# ProPrj_neopixel-seven-segment-display.net
KiCad netlist of a schematic drawn in EasyEDA Pro
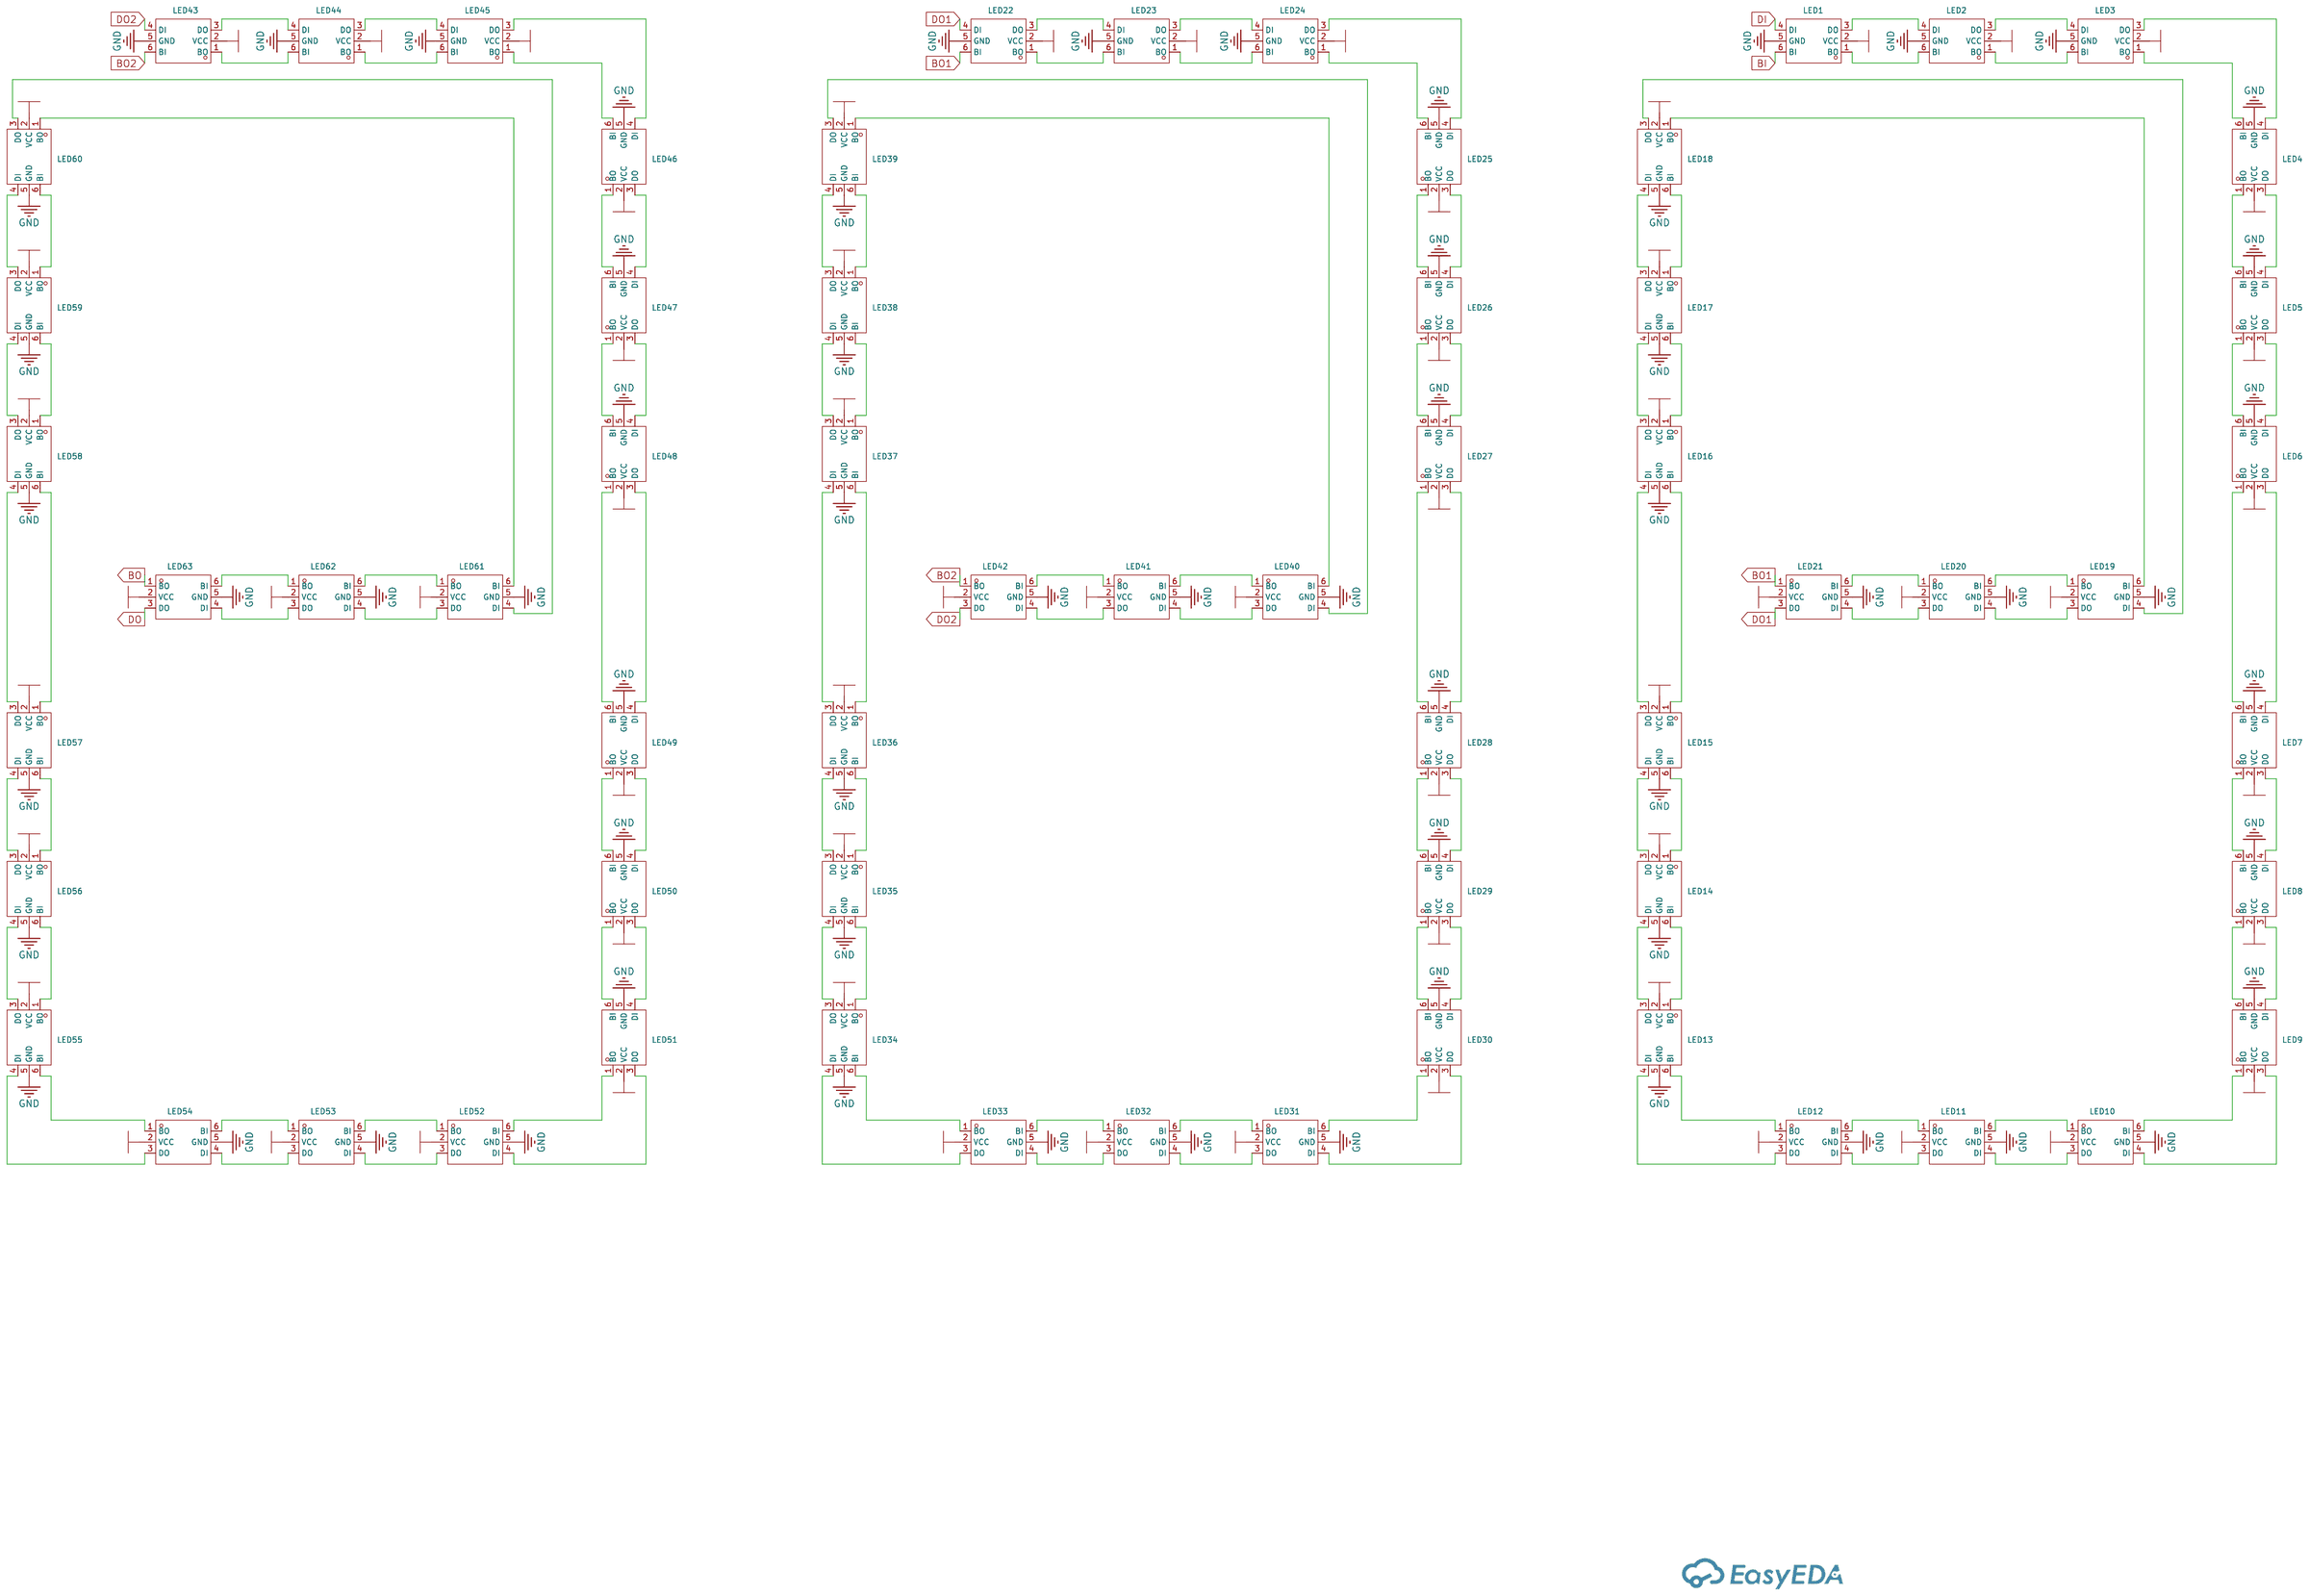
[diagram p0: LEDs]
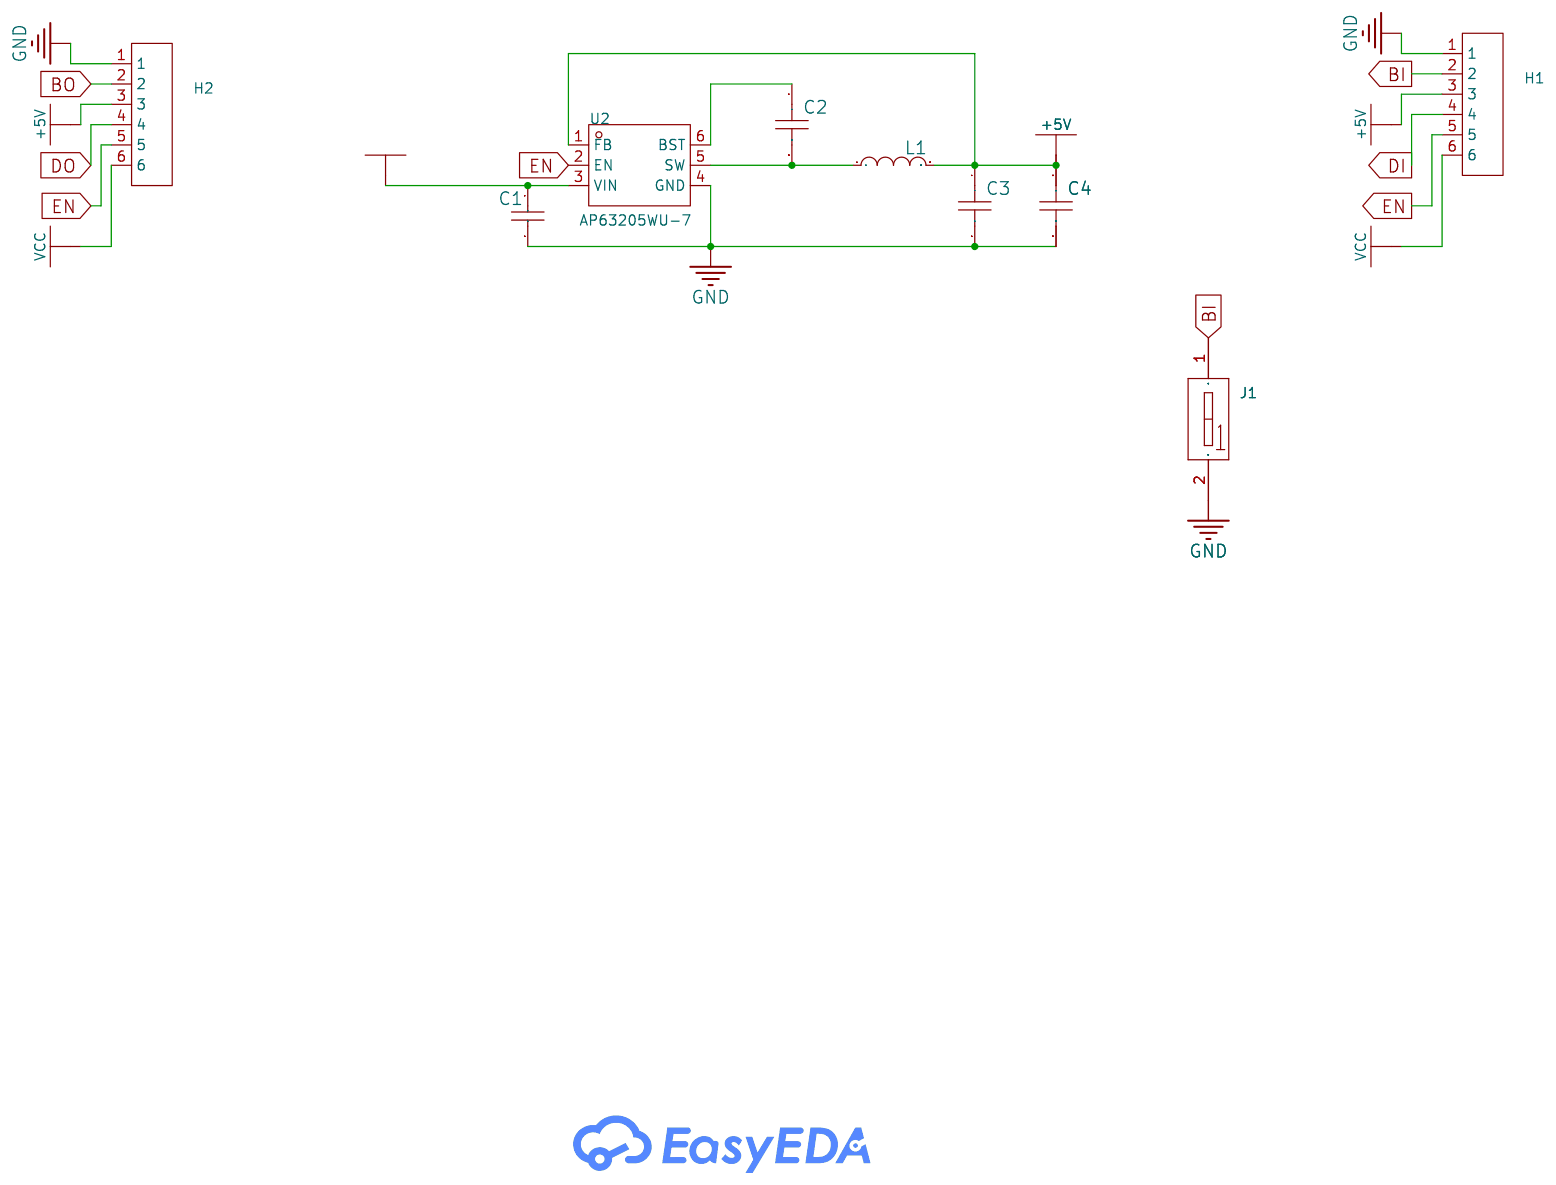
[diagram p1: Components]

(export (version "E")
  (design (tool "Eeschema 10.0.6"))
  (components
    (comp (ref "LED1")
      (value "WS2813B-V5")
      (footprint "easyedapro:LED-SMD_6P-L5.0-W5.0-TL")
      (fields (field (name "Manufacturer") "worldsemi"))
      (libsource (lib "easyedapro") (part "WS2813B-V5"))
    )
    (comp (ref "LED2")
      (value "WS2813B-V5")
      (footprint "easyedapro:LED-SMD_6P-L5.0-W5.0-TL")
      (fields (field (name "Manufacturer") "worldsemi"))
      (libsource (lib "easyedapro") (part "WS2813B-V5"))
    )
    (comp (ref "LED3")
      (value "WS2813B-V5")
      (footprint "easyedapro:LED-SMD_6P-L5.0-W5.0-TL")
      (fields (field (name "Manufacturer") "worldsemi"))
      (libsource (lib "easyedapro") (part "WS2813B-V5"))
    )
    (comp (ref "LED4")
      (value "WS2813B-V5")
      (footprint "easyedapro:LED-SMD_6P-L5.0-W5.0-TL")
      (fields (field (name "Manufacturer") "worldsemi"))
      (libsource (lib "easyedapro") (part "WS2813B-V5"))
    )
    (comp (ref "LED5")
      (value "WS2813B-V5")
      (footprint "easyedapro:LED-SMD_6P-L5.0-W5.0-TL")
      (fields (field (name "Manufacturer") "worldsemi"))
      (libsource (lib "easyedapro") (part "WS2813B-V5"))
    )
    (comp (ref "LED6")
      (value "WS2813B-V5")
      (footprint "easyedapro:LED-SMD_6P-L5.0-W5.0-TL")
      (fields (field (name "Manufacturer") "worldsemi"))
      (libsource (lib "easyedapro") (part "WS2813B-V5"))
    )
    (comp (ref "LED7")
      (value "WS2813B-V5")
      (footprint "easyedapro:LED-SMD_6P-L5.0-W5.0-TL")
      (fields (field (name "Manufacturer") "worldsemi"))
      (libsource (lib "easyedapro") (part "WS2813B-V5"))
    )
    (comp (ref "LED8")
      (value "WS2813B-V5")
      (footprint "easyedapro:LED-SMD_6P-L5.0-W5.0-TL")
      (fields (field (name "Manufacturer") "worldsemi"))
      (libsource (lib "easyedapro") (part "WS2813B-V5"))
    )
    (comp (ref "LED9")
      (value "WS2813B-V5")
      (footprint "easyedapro:LED-SMD_6P-L5.0-W5.0-TL")
      (fields (field (name "Manufacturer") "worldsemi"))
      (libsource (lib "easyedapro") (part "WS2813B-V5"))
    )
    (comp (ref "LED10")
      (value "WS2813B-V5")
      (footprint "easyedapro:LED-SMD_6P-L5.0-W5.0-TL")
      (fields (field (name "Manufacturer") "worldsemi"))
      (libsource (lib "easyedapro") (part "WS2813B-V5"))
    )
    (comp (ref "LED11")
      (value "WS2813B-V5")
      (footprint "easyedapro:LED-SMD_6P-L5.0-W5.0-TL")
      (fields (field (name "Manufacturer") "worldsemi"))
      (libsource (lib "easyedapro") (part "WS2813B-V5"))
    )
    (comp (ref "LED12")
      (value "WS2813B-V5")
      (footprint "easyedapro:LED-SMD_6P-L5.0-W5.0-TL")
      (fields (field (name "Manufacturer") "worldsemi"))
      (libsource (lib "easyedapro") (part "WS2813B-V5"))
    )
    (comp (ref "LED13")
      (value "WS2813B-V5")
      (footprint "easyedapro:LED-SMD_6P-L5.0-W5.0-TL")
      (fields (field (name "Manufacturer") "worldsemi"))
      (libsource (lib "easyedapro") (part "WS2813B-V5"))
    )
    (comp (ref "LED14")
      (value "WS2813B-V5")
      (footprint "easyedapro:LED-SMD_6P-L5.0-W5.0-TL")
      (fields (field (name "Manufacturer") "worldsemi"))
      (libsource (lib "easyedapro") (part "WS2813B-V5"))
    )
    (comp (ref "LED15")
      (value "WS2813B-V5")
      (footprint "easyedapro:LED-SMD_6P-L5.0-W5.0-TL")
      (fields (field (name "Manufacturer") "worldsemi"))
      (libsource (lib "easyedapro") (part "WS2813B-V5"))
    )
    (comp (ref "LED16")
      (value "WS2813B-V5")
      (footprint "easyedapro:LED-SMD_6P-L5.0-W5.0-TL")
      (fields (field (name "Manufacturer") "worldsemi"))
      (libsource (lib "easyedapro") (part "WS2813B-V5"))
    )
    (comp (ref "LED17")
      (value "WS2813B-V5")
      (footprint "easyedapro:LED-SMD_6P-L5.0-W5.0-TL")
      (fields (field (name "Manufacturer") "worldsemi"))
      (libsource (lib "easyedapro") (part "WS2813B-V5"))
    )
    (comp (ref "LED18")
      (value "WS2813B-V5")
      (footprint "easyedapro:LED-SMD_6P-L5.0-W5.0-TL")
      (fields (field (name "Manufacturer") "worldsemi"))
      (libsource (lib "easyedapro") (part "WS2813B-V5"))
    )
    (comp (ref "LED19")
      (value "WS2813B-V5")
      (footprint "easyedapro:LED-SMD_6P-L5.0-W5.0-TL")
      (fields (field (name "Manufacturer") "worldsemi"))
      (libsource (lib "easyedapro") (part "WS2813B-V5"))
    )
    (comp (ref "LED20")
      (value "WS2813B-V5")
      (footprint "easyedapro:LED-SMD_6P-L5.0-W5.0-TL")
      (fields (field (name "Manufacturer") "worldsemi"))
      (libsource (lib "easyedapro") (part "WS2813B-V5"))
    )
    (comp (ref "LED21")
      (value "WS2813B-V5")
      (footprint "easyedapro:LED-SMD_6P-L5.0-W5.0-TL")
      (fields (field (name "Manufacturer") "worldsemi"))
      (libsource (lib "easyedapro") (part "WS2813B-V5"))
    )
    (comp (ref "LED22")
      (value "WS2813B-V5")
      (footprint "easyedapro:LED-SMD_6P-L5.0-W5.0-TL")
      (fields (field (name "Manufacturer") "worldsemi"))
      (libsource (lib "easyedapro") (part "WS2813B-V5"))
    )
    (comp (ref "LED23")
      (value "WS2813B-V5")
      (footprint "easyedapro:LED-SMD_6P-L5.0-W5.0-TL")
      (fields (field (name "Manufacturer") "worldsemi"))
      (libsource (lib "easyedapro") (part "WS2813B-V5"))
    )
    (comp (ref "LED24")
      (value "WS2813B-V5")
      (footprint "easyedapro:LED-SMD_6P-L5.0-W5.0-TL")
      (fields (field (name "Manufacturer") "worldsemi"))
      (libsource (lib "easyedapro") (part "WS2813B-V5"))
    )
    (comp (ref "LED25")
      (value "WS2813B-V5")
      (footprint "easyedapro:LED-SMD_6P-L5.0-W5.0-TL")
      (fields (field (name "Manufacturer") "worldsemi"))
      (libsource (lib "easyedapro") (part "WS2813B-V5"))
    )
    (comp (ref "LED26")
      (value "WS2813B-V5")
      (footprint "easyedapro:LED-SMD_6P-L5.0-W5.0-TL")
      (fields (field (name "Manufacturer") "worldsemi"))
      (libsource (lib "easyedapro") (part "WS2813B-V5"))
    )
    (comp (ref "LED27")
      (value "WS2813B-V5")
      (footprint "easyedapro:LED-SMD_6P-L5.0-W5.0-TL")
      (fields (field (name "Manufacturer") "worldsemi"))
      (libsource (lib "easyedapro") (part "WS2813B-V5"))
    )
    (comp (ref "LED28")
      (value "WS2813B-V5")
      (footprint "easyedapro:LED-SMD_6P-L5.0-W5.0-TL")
      (fields (field (name "Manufacturer") "worldsemi"))
      (libsource (lib "easyedapro") (part "WS2813B-V5"))
    )
    (comp (ref "LED29")
      (value "WS2813B-V5")
      (footprint "easyedapro:LED-SMD_6P-L5.0-W5.0-TL")
      (fields (field (name "Manufacturer") "worldsemi"))
      (libsource (lib "easyedapro") (part "WS2813B-V5"))
    )
    (comp (ref "LED30")
      (value "WS2813B-V5")
      (footprint "easyedapro:LED-SMD_6P-L5.0-W5.0-TL")
      (fields (field (name "Manufacturer") "worldsemi"))
      (libsource (lib "easyedapro") (part "WS2813B-V5"))
    )
    (comp (ref "LED31")
      (value "WS2813B-V5")
      (footprint "easyedapro:LED-SMD_6P-L5.0-W5.0-TL")
      (fields (field (name "Manufacturer") "worldsemi"))
      (libsource (lib "easyedapro") (part "WS2813B-V5"))
    )
    (comp (ref "LED32")
      (value "WS2813B-V5")
      (footprint "easyedapro:LED-SMD_6P-L5.0-W5.0-TL")
      (fields (field (name "Manufacturer") "worldsemi"))
      (libsource (lib "easyedapro") (part "WS2813B-V5"))
    )
    (comp (ref "LED33")
      (value "WS2813B-V5")
      (footprint "easyedapro:LED-SMD_6P-L5.0-W5.0-TL")
      (fields (field (name "Manufacturer") "worldsemi"))
      (libsource (lib "easyedapro") (part "WS2813B-V5"))
    )
    (comp (ref "LED34")
      (value "WS2813B-V5")
      (footprint "easyedapro:LED-SMD_6P-L5.0-W5.0-TL")
      (fields (field (name "Manufacturer") "worldsemi"))
      (libsource (lib "easyedapro") (part "WS2813B-V5"))
    )
    (comp (ref "LED35")
      (value "WS2813B-V5")
      (footprint "easyedapro:LED-SMD_6P-L5.0-W5.0-TL")
      (fields (field (name "Manufacturer") "worldsemi"))
      (libsource (lib "easyedapro") (part "WS2813B-V5"))
    )
    (comp (ref "LED36")
      (value "WS2813B-V5")
      (footprint "easyedapro:LED-SMD_6P-L5.0-W5.0-TL")
      (fields (field (name "Manufacturer") "worldsemi"))
      (libsource (lib "easyedapro") (part "WS2813B-V5"))
    )
    (comp (ref "LED37")
      (value "WS2813B-V5")
      (footprint "easyedapro:LED-SMD_6P-L5.0-W5.0-TL")
      (fields (field (name "Manufacturer") "worldsemi"))
      (libsource (lib "easyedapro") (part "WS2813B-V5"))
    )
    (comp (ref "LED38")
      (value "WS2813B-V5")
      (footprint "easyedapro:LED-SMD_6P-L5.0-W5.0-TL")
      (fields (field (name "Manufacturer") "worldsemi"))
      (libsource (lib "easyedapro") (part "WS2813B-V5"))
    )
    (comp (ref "LED39")
      (value "WS2813B-V5")
      (footprint "easyedapro:LED-SMD_6P-L5.0-W5.0-TL")
      (fields (field (name "Manufacturer") "worldsemi"))
      (libsource (lib "easyedapro") (part "WS2813B-V5"))
    )
    (comp (ref "LED40")
      (value "WS2813B-V5")
      (footprint "easyedapro:LED-SMD_6P-L5.0-W5.0-TL")
      (fields (field (name "Manufacturer") "worldsemi"))
      (libsource (lib "easyedapro") (part "WS2813B-V5"))
    )
    (comp (ref "LED41")
      (value "WS2813B-V5")
      (footprint "easyedapro:LED-SMD_6P-L5.0-W5.0-TL")
      (fields (field (name "Manufacturer") "worldsemi"))
      (libsource (lib "easyedapro") (part "WS2813B-V5"))
    )
    (comp (ref "LED42")
      (value "WS2813B-V5")
      (footprint "easyedapro:LED-SMD_6P-L5.0-W5.0-TL")
      (fields (field (name "Manufacturer") "worldsemi"))
      (libsource (lib "easyedapro") (part "WS2813B-V5"))
    )
    (comp (ref "LED43")
      (value "WS2813B-V5")
      (footprint "easyedapro:LED-SMD_6P-L5.0-W5.0-TL")
      (fields (field (name "Manufacturer") "worldsemi"))
      (libsource (lib "easyedapro") (part "WS2813B-V5"))
    )
    (comp (ref "LED44")
      (value "WS2813B-V5")
      (footprint "easyedapro:LED-SMD_6P-L5.0-W5.0-TL")
      (fields (field (name "Manufacturer") "worldsemi"))
      (libsource (lib "easyedapro") (part "WS2813B-V5"))
    )
    (comp (ref "LED45")
      (value "WS2813B-V5")
      (footprint "easyedapro:LED-SMD_6P-L5.0-W5.0-TL")
      (fields (field (name "Manufacturer") "worldsemi"))
      (libsource (lib "easyedapro") (part "WS2813B-V5"))
    )
    (comp (ref "LED46")
      (value "WS2813B-V5")
      (footprint "easyedapro:LED-SMD_6P-L5.0-W5.0-TL")
      (fields (field (name "Manufacturer") "worldsemi"))
      (libsource (lib "easyedapro") (part "WS2813B-V5"))
    )
    (comp (ref "LED47")
      (value "WS2813B-V5")
      (footprint "easyedapro:LED-SMD_6P-L5.0-W5.0-TL")
      (fields (field (name "Manufacturer") "worldsemi"))
      (libsource (lib "easyedapro") (part "WS2813B-V5"))
    )
    (comp (ref "LED48")
      (value "WS2813B-V5")
      (footprint "easyedapro:LED-SMD_6P-L5.0-W5.0-TL")
      (fields (field (name "Manufacturer") "worldsemi"))
      (libsource (lib "easyedapro") (part "WS2813B-V5"))
    )
    (comp (ref "LED49")
      (value "WS2813B-V5")
      (footprint "easyedapro:LED-SMD_6P-L5.0-W5.0-TL")
      (fields (field (name "Manufacturer") "worldsemi"))
      (libsource (lib "easyedapro") (part "WS2813B-V5"))
    )
    (comp (ref "LED50")
      (value "WS2813B-V5")
      (footprint "easyedapro:LED-SMD_6P-L5.0-W5.0-TL")
      (fields (field (name "Manufacturer") "worldsemi"))
      (libsource (lib "easyedapro") (part "WS2813B-V5"))
    )
    (comp (ref "LED51")
      (value "WS2813B-V5")
      (footprint "easyedapro:LED-SMD_6P-L5.0-W5.0-TL")
      (fields (field (name "Manufacturer") "worldsemi"))
      (libsource (lib "easyedapro") (part "WS2813B-V5"))
    )
    (comp (ref "LED52")
      (value "WS2813B-V5")
      (footprint "easyedapro:LED-SMD_6P-L5.0-W5.0-TL")
      (fields (field (name "Manufacturer") "worldsemi"))
      (libsource (lib "easyedapro") (part "WS2813B-V5"))
    )
    (comp (ref "LED53")
      (value "WS2813B-V5")
      (footprint "easyedapro:LED-SMD_6P-L5.0-W5.0-TL")
      (fields (field (name "Manufacturer") "worldsemi"))
      (libsource (lib "easyedapro") (part "WS2813B-V5"))
    )
    (comp (ref "LED54")
      (value "WS2813B-V5")
      (footprint "easyedapro:LED-SMD_6P-L5.0-W5.0-TL")
      (fields (field (name "Manufacturer") "worldsemi"))
      (libsource (lib "easyedapro") (part "WS2813B-V5"))
    )
    (comp (ref "LED55")
      (value "WS2813B-V5")
      (footprint "easyedapro:LED-SMD_6P-L5.0-W5.0-TL")
      (fields (field (name "Manufacturer") "worldsemi"))
      (libsource (lib "easyedapro") (part "WS2813B-V5"))
    )
    (comp (ref "LED56")
      (value "WS2813B-V5")
      (footprint "easyedapro:LED-SMD_6P-L5.0-W5.0-TL")
      (fields (field (name "Manufacturer") "worldsemi"))
      (libsource (lib "easyedapro") (part "WS2813B-V5"))
    )
    (comp (ref "LED57")
      (value "WS2813B-V5")
      (footprint "easyedapro:LED-SMD_6P-L5.0-W5.0-TL")
      (fields (field (name "Manufacturer") "worldsemi"))
      (libsource (lib "easyedapro") (part "WS2813B-V5"))
    )
    (comp (ref "LED58")
      (value "WS2813B-V5")
      (footprint "easyedapro:LED-SMD_6P-L5.0-W5.0-TL")
      (fields (field (name "Manufacturer") "worldsemi"))
      (libsource (lib "easyedapro") (part "WS2813B-V5"))
    )
    (comp (ref "LED59")
      (value "WS2813B-V5")
      (footprint "easyedapro:LED-SMD_6P-L5.0-W5.0-TL")
      (fields (field (name "Manufacturer") "worldsemi"))
      (libsource (lib "easyedapro") (part "WS2813B-V5"))
    )
    (comp (ref "LED60")
      (value "WS2813B-V5")
      (footprint "easyedapro:LED-SMD_6P-L5.0-W5.0-TL")
      (fields (field (name "Manufacturer") "worldsemi"))
      (libsource (lib "easyedapro") (part "WS2813B-V5"))
    )
    (comp (ref "LED61")
      (value "WS2813B-V5")
      (footprint "easyedapro:LED-SMD_6P-L5.0-W5.0-TL")
      (fields (field (name "Manufacturer") "worldsemi"))
      (libsource (lib "easyedapro") (part "WS2813B-V5"))
    )
    (comp (ref "LED62")
      (value "WS2813B-V5")
      (footprint "easyedapro:LED-SMD_6P-L5.0-W5.0-TL")
      (fields (field (name "Manufacturer") "worldsemi"))
      (libsource (lib "easyedapro") (part "WS2813B-V5"))
    )
    (comp (ref "LED63")
      (value "WS2813B-V5")
      (footprint "easyedapro:LED-SMD_6P-L5.0-W5.0-TL")
      (fields (field (name "Manufacturer") "worldsemi"))
      (libsource (lib "easyedapro") (part "WS2813B-V5"))
    )
    (comp (ref "C1")
      (value "10uF")
      (footprint "easyedapro:C1210")
      (fields
        (field (name "Manufacturer Part") "CL32B106KAJNNNE")
        (field (name "Manufacturer") "SAMSUNG(三星)")
      )
      (libsource (lib "easyedapro") (part "CL32B106KAJNNNE"))
    )
    (comp (ref "C2")
      (value "100nF")
      (footprint "easyedapro:C1206")
      (fields (field (name "Manufacturer Part") "1206N104J500CT") (field (name "Manufacturer") "Walsin(华新科)"))
      (libsource (lib "easyedapro") (part "1206N104J500"))
    )
    (comp (ref "C3")
      (value "22uF")
      (footprint "easyedapro:C1210")
      (fields
        (field (name "Manufacturer Part") "CL32B226KAJNNNE")
        (field (name "Manufacturer") "SAMSUNG(三星)")
      )
      (libsource (lib "easyedapro") (part "CL32B226KAJNNNE"))
    )
    (comp (ref "C4")
      (value "22uF")
      (footprint "easyedapro:C1210")
      (fields
        (field (name "Manufacturer Part") "CL32B226KAJNNNE")
        (field (name "Manufacturer") "SAMSUNG(三星)")
      )
      (libsource (lib "easyedapro") (part "CL32B226KAJNNNE"))
    )
    (comp (ref "H1")
      (value "DB2EVC-2.54-6P-GN")
      (footprint "easyedapro:CONN-TH_6P-P2.54_DIBO_DB2EVC-2.54-6P-GN")
      (fields (field (name "Manufacturer") "DORABO(地博电气)"))
      (libsource (lib "easyedapro") (part "DB2EVC-2.54-6P-GN"))
    )
    (comp (ref "H2")
      (value "DB2EVC-2.54-6P-GN")
      (footprint "easyedapro:CONN-TH_6P-P2.54_DIBO_DB2EVC-2.54-6P-GN")
      (fields (field (name "Manufacturer") "DORABO(地博电气)"))
      (libsource (lib "easyedapro") (part "DB2EVC-2.54-6P-GN"))
    )
    (comp (ref "J1")
      (value "DSWB01LHGET")
      (footprint "easyedapro:SW-TH_DSWB01LHGET")
      (description "Type:Slide, Rocked Circuit:SPST Number of Positions:1 Lead Pitch:- Operating Life:- Color:Red")
      (fields (field (name "Manufacturer") "YE"))
      (libsource (lib "easyedapro") (part "DSWB01LHGET"))
    )
    (comp (ref "L1")
      (value "4.7uH")
      (footprint "easyedapro:IND-SMD_L3.2-W2.5_CMI3225XX")
      (fields
        (field (name "Manufacturer Part") "DFE322520FD-4R7M=P2")
        (field (name "Manufacturer") "muRata(村田)")
      )
      (libsource (lib "easyedapro") (part "DFE322520FD-4R7M=P2"))
    )
    (comp (ref "U2")
      (value "AP63205WU-7")
      (footprint "easyedapro:TSOT-23-6_L2.9-W1.6-P0.95-LS2.8-BL")
      (fields (field (name "Manufacturer") "DIODES(美台)"))
      (libsource (lib "easyedapro") (part "AP63205WU-7"))
    )
  )
  (nets
    (net (code "1") (name "+5V") (class "Default")
      (node (ref "C3") (pin "1") (pinfunction "1_1") (pintype "unspecified"))
      (node (ref "C4") (pin "1") (pinfunction "1_1") (pintype "unspecified"))
      (node (ref "H1") (pin "3") (pinfunction "3_3") (pintype "unspecified"))
      (node (ref "H2") (pin "3") (pinfunction "3_3") (pintype "unspecified"))
      (node (ref "L1") (pin "2") (pinfunction "2_2") (pintype "unspecified"))
      (node (ref "LED1") (pin "2") (pinfunction "VCC_2") (pintype "input"))
      (node (ref "LED10") (pin "2") (pinfunction "VCC_2") (pintype "input"))
      (node (ref "LED11") (pin "2") (pinfunction "VCC_2") (pintype "input"))
      (node (ref "LED12") (pin "2") (pinfunction "VCC_2") (pintype "input"))
      (node (ref "LED13") (pin "2") (pinfunction "VCC_2") (pintype "input"))
      (node (ref "LED14") (pin "2") (pinfunction "VCC_2") (pintype "input"))
      (node (ref "LED15") (pin "2") (pinfunction "VCC_2") (pintype "input"))
      (node (ref "LED16") (pin "2") (pinfunction "VCC_2") (pintype "input"))
      (node (ref "LED17") (pin "2") (pinfunction "VCC_2") (pintype "input"))
      (node (ref "LED18") (pin "2") (pinfunction "VCC_2") (pintype "input"))
      (node (ref "LED19") (pin "2") (pinfunction "VCC_2") (pintype "input"))
      (node (ref "LED2") (pin "2") (pinfunction "VCC_2") (pintype "input"))
      (node (ref "LED20") (pin "2") (pinfunction "VCC_2") (pintype "input"))
      (node (ref "LED21") (pin "2") (pinfunction "VCC_2") (pintype "input"))
      (node (ref "LED22") (pin "2") (pinfunction "VCC_2") (pintype "input"))
      (node (ref "LED23") (pin "2") (pinfunction "VCC_2") (pintype "input"))
      (node (ref "LED24") (pin "2") (pinfunction "VCC_2") (pintype "input"))
      (node (ref "LED25") (pin "2") (pinfunction "VCC_2") (pintype "input"))
      (node (ref "LED26") (pin "2") (pinfunction "VCC_2") (pintype "input"))
      (node (ref "LED27") (pin "2") (pinfunction "VCC_2") (pintype "input"))
      (node (ref "LED28") (pin "2") (pinfunction "VCC_2") (pintype "input"))
      (node (ref "LED29") (pin "2") (pinfunction "VCC_2") (pintype "input"))
      (node (ref "LED3") (pin "2") (pinfunction "VCC_2") (pintype "input"))
      (node (ref "LED30") (pin "2") (pinfunction "VCC_2") (pintype "input"))
      (node (ref "LED31") (pin "2") (pinfunction "VCC_2") (pintype "input"))
      (node (ref "LED32") (pin "2") (pinfunction "VCC_2") (pintype "input"))
      (node (ref "LED33") (pin "2") (pinfunction "VCC_2") (pintype "input"))
      (node (ref "LED34") (pin "2") (pinfunction "VCC_2") (pintype "input"))
      (node (ref "LED35") (pin "2") (pinfunction "VCC_2") (pintype "input"))
      (node (ref "LED36") (pin "2") (pinfunction "VCC_2") (pintype "input"))
      (node (ref "LED37") (pin "2") (pinfunction "VCC_2") (pintype "input"))
      (node (ref "LED38") (pin "2") (pinfunction "VCC_2") (pintype "input"))
      (node (ref "LED39") (pin "2") (pinfunction "VCC_2") (pintype "input"))
      (node (ref "LED4") (pin "2") (pinfunction "VCC_2") (pintype "input"))
      (node (ref "LED40") (pin "2") (pinfunction "VCC_2") (pintype "input"))
      (node (ref "LED41") (pin "2") (pinfunction "VCC_2") (pintype "input"))
      (node (ref "LED42") (pin "2") (pinfunction "VCC_2") (pintype "input"))
      (node (ref "LED43") (pin "2") (pinfunction "VCC_2") (pintype "input"))
      (node (ref "LED44") (pin "2") (pinfunction "VCC_2") (pintype "input"))
      (node (ref "LED45") (pin "2") (pinfunction "VCC_2") (pintype "input"))
      (node (ref "LED46") (pin "2") (pinfunction "VCC_2") (pintype "input"))
      (node (ref "LED47") (pin "2") (pinfunction "VCC_2") (pintype "input"))
      (node (ref "LED48") (pin "2") (pinfunction "VCC_2") (pintype "input"))
      (node (ref "LED49") (pin "2") (pinfunction "VCC_2") (pintype "input"))
      (node (ref "LED5") (pin "2") (pinfunction "VCC_2") (pintype "input"))
      (node (ref "LED50") (pin "2") (pinfunction "VCC_2") (pintype "input"))
      (node (ref "LED51") (pin "2") (pinfunction "VCC_2") (pintype "input"))
      (node (ref "LED52") (pin "2") (pinfunction "VCC_2") (pintype "input"))
      (node (ref "LED53") (pin "2") (pinfunction "VCC_2") (pintype "input"))
      (node (ref "LED54") (pin "2") (pinfunction "VCC_2") (pintype "input"))
      (node (ref "LED55") (pin "2") (pinfunction "VCC_2") (pintype "input"))
      (node (ref "LED56") (pin "2") (pinfunction "VCC_2") (pintype "input"))
      (node (ref "LED57") (pin "2") (pinfunction "VCC_2") (pintype "input"))
      (node (ref "LED58") (pin "2") (pinfunction "VCC_2") (pintype "input"))
      (node (ref "LED59") (pin "2") (pinfunction "VCC_2") (pintype "input"))
      (node (ref "LED6") (pin "2") (pinfunction "VCC_2") (pintype "input"))
      (node (ref "LED60") (pin "2") (pinfunction "VCC_2") (pintype "input"))
      (node (ref "LED61") (pin "2") (pinfunction "VCC_2") (pintype "input"))
      (node (ref "LED62") (pin "2") (pinfunction "VCC_2") (pintype "input"))
      (node (ref "LED63") (pin "2") (pinfunction "VCC_2") (pintype "input"))
      (node (ref "LED7") (pin "2") (pinfunction "VCC_2") (pintype "input"))
      (node (ref "LED8") (pin "2") (pinfunction "VCC_2") (pintype "input"))
      (node (ref "LED9") (pin "2") (pinfunction "VCC_2") (pintype "input"))
      (node (ref "U2") (pin "1") (pinfunction "FB_1") (pintype "input"))
    )
    (net (code "2") (name "BI") (class "Default")
      (node (ref "H1") (pin "2") (pinfunction "2_2") (pintype "unspecified"))
      (node (ref "J1") (pin "1") (pinfunction "A1_1") (pintype "input"))
      (node (ref "LED1") (pin "6") (pinfunction "BI_6") (pintype "input"))
    )
    (net (code "3") (name "BO") (class "Default")
      (node (ref "H2") (pin "2") (pinfunction "2_2") (pintype "unspecified"))
      (node (ref "LED63") (pin "1") (pinfunction "BO_1") (pintype "input"))
    )
    (net (code "4") (name "BO1") (class "Default")
      (node (ref "LED21") (pin "1") (pinfunction "BO_1") (pintype "input"))
      (node (ref "LED22") (pin "6") (pinfunction "BI_6") (pintype "input"))
    )
    (net (code "5") (name "BO2") (class "Default")
      (node (ref "LED42") (pin "1") (pinfunction "BO_1") (pintype "input"))
      (node (ref "LED43") (pin "6") (pinfunction "BI_6") (pintype "input"))
    )
    (net (code "6") (name "DI") (class "Default")
      (node (ref "H1") (pin "4") (pinfunction "4_4") (pintype "unspecified"))
      (node (ref "LED1") (pin "4") (pinfunction "DI_4") (pintype "input"))
    )
    (net (code "7") (name "DO") (class "Default")
      (node (ref "H2") (pin "4") (pinfunction "4_4") (pintype "unspecified"))
      (node (ref "LED63") (pin "3") (pinfunction "DO_3") (pintype "input"))
    )
    (net (code "8") (name "DO1") (class "Default")
      (node (ref "LED21") (pin "3") (pinfunction "DO_3") (pintype "input"))
      (node (ref "LED22") (pin "4") (pinfunction "DI_4") (pintype "input"))
    )
    (net (code "9") (name "DO2") (class "Default")
      (node (ref "LED42") (pin "3") (pinfunction "DO_3") (pintype "input"))
      (node (ref "LED43") (pin "4") (pinfunction "DI_4") (pintype "input"))
    )
    (net (code "10") (name "EN") (class "Default")
      (node (ref "H1") (pin "5") (pinfunction "5_5") (pintype "unspecified"))
      (node (ref "H2") (pin "5") (pinfunction "5_5") (pintype "unspecified"))
      (node (ref "U2") (pin "2") (pinfunction "EN_2") (pintype "input"))
    )
    (net (code "11") (name "GND") (class "Default")
      (node (ref "C1") (pin "2") (pinfunction "2_2") (pintype "input"))
      (node (ref "C3") (pin "2") (pinfunction "2_2") (pintype "unspecified"))
      (node (ref "C4") (pin "2") (pinfunction "2_2") (pintype "unspecified"))
      (node (ref "H1") (pin "1") (pinfunction "1_1") (pintype "unspecified"))
      (node (ref "H2") (pin "1") (pinfunction "1_1") (pintype "unspecified"))
      (node (ref "J1") (pin "2") (pinfunction "2_2") (pintype "input"))
      (node (ref "LED1") (pin "5") (pinfunction "GND_5") (pintype "input"))
      (node (ref "LED10") (pin "5") (pinfunction "GND_5") (pintype "input"))
      (node (ref "LED11") (pin "5") (pinfunction "GND_5") (pintype "input"))
      (node (ref "LED12") (pin "5") (pinfunction "GND_5") (pintype "input"))
      (node (ref "LED13") (pin "5") (pinfunction "GND_5") (pintype "input"))
      (node (ref "LED14") (pin "5") (pinfunction "GND_5") (pintype "input"))
      (node (ref "LED15") (pin "5") (pinfunction "GND_5") (pintype "input"))
      (node (ref "LED16") (pin "5") (pinfunction "GND_5") (pintype "input"))
      (node (ref "LED17") (pin "5") (pinfunction "GND_5") (pintype "input"))
      (node (ref "LED18") (pin "5") (pinfunction "GND_5") (pintype "input"))
      (node (ref "LED19") (pin "5") (pinfunction "GND_5") (pintype "input"))
      (node (ref "LED2") (pin "5") (pinfunction "GND_5") (pintype "input"))
      (node (ref "LED20") (pin "5") (pinfunction "GND_5") (pintype "input"))
      (node (ref "LED21") (pin "5") (pinfunction "GND_5") (pintype "input"))
      (node (ref "LED22") (pin "5") (pinfunction "GND_5") (pintype "input"))
      (node (ref "LED23") (pin "5") (pinfunction "GND_5") (pintype "input"))
      (node (ref "LED24") (pin "5") (pinfunction "GND_5") (pintype "input"))
      (node (ref "LED25") (pin "5") (pinfunction "GND_5") (pintype "input"))
      (node (ref "LED26") (pin "5") (pinfunction "GND_5") (pintype "input"))
      (node (ref "LED27") (pin "5") (pinfunction "GND_5") (pintype "input"))
      (node (ref "LED28") (pin "5") (pinfunction "GND_5") (pintype "input"))
      (node (ref "LED29") (pin "5") (pinfunction "GND_5") (pintype "input"))
      (node (ref "LED3") (pin "5") (pinfunction "GND_5") (pintype "input"))
      (node (ref "LED30") (pin "5") (pinfunction "GND_5") (pintype "input"))
      (node (ref "LED31") (pin "5") (pinfunction "GND_5") (pintype "input"))
      (node (ref "LED32") (pin "5") (pinfunction "GND_5") (pintype "input"))
      (node (ref "LED33") (pin "5") (pinfunction "GND_5") (pintype "input"))
      (node (ref "LED34") (pin "5") (pinfunction "GND_5") (pintype "input"))
      (node (ref "LED35") (pin "5") (pinfunction "GND_5") (pintype "input"))
      (node (ref "LED36") (pin "5") (pinfunction "GND_5") (pintype "input"))
      (node (ref "LED37") (pin "5") (pinfunction "GND_5") (pintype "input"))
      (node (ref "LED38") (pin "5") (pinfunction "GND_5") (pintype "input"))
      (node (ref "LED39") (pin "5") (pinfunction "GND_5") (pintype "input"))
      (node (ref "LED4") (pin "5") (pinfunction "GND_5") (pintype "input"))
      (node (ref "LED40") (pin "5") (pinfunction "GND_5") (pintype "input"))
      (node (ref "LED41") (pin "5") (pinfunction "GND_5") (pintype "input"))
      (node (ref "LED42") (pin "5") (pinfunction "GND_5") (pintype "input"))
      (node (ref "LED43") (pin "5") (pinfunction "GND_5") (pintype "input"))
      (node (ref "LED44") (pin "5") (pinfunction "GND_5") (pintype "input"))
      (node (ref "LED45") (pin "5") (pinfunction "GND_5") (pintype "input"))
      (node (ref "LED46") (pin "5") (pinfunction "GND_5") (pintype "input"))
      (node (ref "LED47") (pin "5") (pinfunction "GND_5") (pintype "input"))
      (node (ref "LED48") (pin "5") (pinfunction "GND_5") (pintype "input"))
      (node (ref "LED49") (pin "5") (pinfunction "GND_5") (pintype "input"))
      (node (ref "LED5") (pin "5") (pinfunction "GND_5") (pintype "input"))
      (node (ref "LED50") (pin "5") (pinfunction "GND_5") (pintype "input"))
      (node (ref "LED51") (pin "5") (pinfunction "GND_5") (pintype "input"))
      (node (ref "LED52") (pin "5") (pinfunction "GND_5") (pintype "input"))
      (node (ref "LED53") (pin "5") (pinfunction "GND_5") (pintype "input"))
      (node (ref "LED54") (pin "5") (pinfunction "GND_5") (pintype "input"))
      (node (ref "LED55") (pin "5") (pinfunction "GND_5") (pintype "input"))
      (node (ref "LED56") (pin "5") (pinfunction "GND_5") (pintype "input"))
      (node (ref "LED57") (pin "5") (pinfunction "GND_5") (pintype "input"))
      (node (ref "LED58") (pin "5") (pinfunction "GND_5") (pintype "input"))
      (node (ref "LED59") (pin "5") (pinfunction "GND_5") (pintype "input"))
      (node (ref "LED6") (pin "5") (pinfunction "GND_5") (pintype "input"))
      (node (ref "LED60") (pin "5") (pinfunction "GND_5") (pintype "input"))
      (node (ref "LED61") (pin "5") (pinfunction "GND_5") (pintype "input"))
      (node (ref "LED62") (pin "5") (pinfunction "GND_5") (pintype "input"))
      (node (ref "LED63") (pin "5") (pinfunction "GND_5") (pintype "input"))
      (node (ref "LED7") (pin "5") (pinfunction "GND_5") (pintype "input"))
      (node (ref "LED8") (pin "5") (pinfunction "GND_5") (pintype "input"))
      (node (ref "LED9") (pin "5") (pinfunction "GND_5") (pintype "input"))
      (node (ref "U2") (pin "4") (pinfunction "GND_4") (pintype "input"))
    )
    (net (code "12") (name "Net-(LED1-BO)") (class "Default")
      (node (ref "LED1") (pin "1") (pinfunction "BO_1") (pintype "input"))
      (node (ref "LED2") (pin "6") (pinfunction "BI_6") (pintype "input"))
    )
    (net (code "13") (name "Net-(LED1-DO)") (class "Default")
      (node (ref "LED1") (pin "3") (pinfunction "DO_3") (pintype "input"))
      (node (ref "LED2") (pin "4") (pinfunction "DI_4") (pintype "input"))
    )
    (net (code "14") (name "Net-(LED2-BO)") (class "Default")
      (node (ref "LED2") (pin "1") (pinfunction "BO_1") (pintype "input"))
      (node (ref "LED3") (pin "6") (pinfunction "BI_6") (pintype "input"))
    )
    (net (code "15") (name "Net-(LED2-DO)") (class "Default")
      (node (ref "LED2") (pin "3") (pinfunction "DO_3") (pintype "input"))
      (node (ref "LED3") (pin "4") (pinfunction "DI_4") (pintype "input"))
    )
    (net (code "16") (name "Net-(LED3-BO)") (class "Default")
      (node (ref "LED3") (pin "1") (pinfunction "BO_1") (pintype "input"))
      (node (ref "LED4") (pin "6") (pinfunction "BI_6") (pintype "input"))
    )
    (net (code "17") (name "Net-(LED3-DO)") (class "Default")
      (node (ref "LED3") (pin "3") (pinfunction "DO_3") (pintype "input"))
      (node (ref "LED4") (pin "4") (pinfunction "DI_4") (pintype "input"))
    )
    (net (code "18") (name "Net-(LED4-BO)") (class "Default")
      (node (ref "LED4") (pin "1") (pinfunction "BO_1") (pintype "input"))
      (node (ref "LED5") (pin "6") (pinfunction "BI_6") (pintype "input"))
    )
    (net (code "19") (name "Net-(LED4-DO)") (class "Default")
      (node (ref "LED4") (pin "3") (pinfunction "DO_3") (pintype "input"))
      (node (ref "LED5") (pin "4") (pinfunction "DI_4") (pintype "input"))
    )
    (net (code "20") (name "Net-(LED5-BO)") (class "Default")
      (node (ref "LED5") (pin "1") (pinfunction "BO_1") (pintype "input"))
      (node (ref "LED6") (pin "6") (pinfunction "BI_6") (pintype "input"))
    )
    (net (code "21") (name "Net-(LED5-DO)") (class "Default")
      (node (ref "LED5") (pin "3") (pinfunction "DO_3") (pintype "input"))
      (node (ref "LED6") (pin "4") (pinfunction "DI_4") (pintype "input"))
    )
    (net (code "22") (name "Net-(LED6-BO)") (class "Default")
      (node (ref "LED6") (pin "1") (pinfunction "BO_1") (pintype "input"))
      (node (ref "LED7") (pin "6") (pinfunction "BI_6") (pintype "input"))
    )
    (net (code "23") (name "Net-(LED6-DO)") (class "Default")
      (node (ref "LED6") (pin "3") (pinfunction "DO_3") (pintype "input"))
      (node (ref "LED7") (pin "4") (pinfunction "DI_4") (pintype "input"))
    )
    (net (code "24") (name "Net-(LED7-BO)") (class "Default")
      (node (ref "LED7") (pin "1") (pinfunction "BO_1") (pintype "input"))
      (node (ref "LED8") (pin "6") (pinfunction "BI_6") (pintype "input"))
    )
    (net (code "25") (name "Net-(LED7-DO)") (class "Default")
      (node (ref "LED7") (pin "3") (pinfunction "DO_3") (pintype "input"))
      (node (ref "LED8") (pin "4") (pinfunction "DI_4") (pintype "input"))
    )
    (net (code "26") (name "Net-(LED8-BO)") (class "Default")
      (node (ref "LED8") (pin "1") (pinfunction "BO_1") (pintype "input"))
      (node (ref "LED9") (pin "6") (pinfunction "BI_6") (pintype "input"))
    )
    (net (code "27") (name "Net-(LED8-DO)") (class "Default")
      (node (ref "LED8") (pin "3") (pinfunction "DO_3") (pintype "input"))
      (node (ref "LED9") (pin "4") (pinfunction "DI_4") (pintype "input"))
    )
    (net (code "28") (name "Net-(LED10-BI)") (class "Default")
      (node (ref "LED10") (pin "6") (pinfunction "BI_6") (pintype "input"))
      (node (ref "LED9") (pin "1") (pinfunction "BO_1") (pintype "input"))
    )
    (net (code "29") (name "Net-(LED10-BO)") (class "Default")
      (node (ref "LED10") (pin "1") (pinfunction "BO_1") (pintype "input"))
      (node (ref "LED11") (pin "6") (pinfunction "BI_6") (pintype "input"))
    )
    (net (code "30") (name "Net-(LED10-DI)") (class "Default")
      (node (ref "LED10") (pin "4") (pinfunction "DI_4") (pintype "input"))
      (node (ref "LED9") (pin "3") (pinfunction "DO_3") (pintype "input"))
    )
    (net (code "31") (name "Net-(LED10-DO)") (class "Default")
      (node (ref "LED10") (pin "3") (pinfunction "DO_3") (pintype "input"))
      (node (ref "LED11") (pin "4") (pinfunction "DI_4") (pintype "input"))
    )
    (net (code "32") (name "Net-(LED11-BO)") (class "Default")
      (node (ref "LED11") (pin "1") (pinfunction "BO_1") (pintype "input"))
      (node (ref "LED12") (pin "6") (pinfunction "BI_6") (pintype "input"))
    )
    (net (code "33") (name "Net-(LED11-DO)") (class "Default")
      (node (ref "LED11") (pin "3") (pinfunction "DO_3") (pintype "input"))
      (node (ref "LED12") (pin "4") (pinfunction "DI_4") (pintype "input"))
    )
    (net (code "34") (name "Net-(LED12-BO)") (class "Default")
      (node (ref "LED12") (pin "1") (pinfunction "BO_1") (pintype "input"))
      (node (ref "LED13") (pin "6") (pinfunction "BI_6") (pintype "input"))
    )
    (net (code "35") (name "Net-(LED12-DO)") (class "Default")
      (node (ref "LED12") (pin "3") (pinfunction "DO_3") (pintype "input"))
      (node (ref "LED13") (pin "4") (pinfunction "DI_4") (pintype "input"))
    )
    (net (code "36") (name "Net-(LED13-BO)") (class "Default")
      (node (ref "LED13") (pin "1") (pinfunction "BO_1") (pintype "input"))
      (node (ref "LED14") (pin "6") (pinfunction "BI_6") (pintype "input"))
    )
    (net (code "37") (name "Net-(LED13-DO)") (class "Default")
      (node (ref "LED13") (pin "3") (pinfunction "DO_3") (pintype "input"))
      (node (ref "LED14") (pin "4") (pinfunction "DI_4") (pintype "input"))
    )
    (net (code "38") (name "Net-(LED14-BO)") (class "Default")
      (node (ref "LED14") (pin "1") (pinfunction "BO_1") (pintype "input"))
      (node (ref "LED15") (pin "6") (pinfunction "BI_6") (pintype "input"))
    )
    (net (code "39") (name "Net-(LED14-DO)") (class "Default")
      (node (ref "LED14") (pin "3") (pinfunction "DO_3") (pintype "input"))
      (node (ref "LED15") (pin "4") (pinfunction "DI_4") (pintype "input"))
    )
    (net (code "40") (name "Net-(LED15-BO)") (class "Default")
      (node (ref "LED15") (pin "1") (pinfunction "BO_1") (pintype "input"))
      (node (ref "LED16") (pin "6") (pinfunction "BI_6") (pintype "input"))
    )
    (net (code "41") (name "Net-(LED15-DO)") (class "Default")
      (node (ref "LED15") (pin "3") (pinfunction "DO_3") (pintype "input"))
      (node (ref "LED16") (pin "4") (pinfunction "DI_4") (pintype "input"))
    )
    (net (code "42") (name "Net-(LED16-BO)") (class "Default")
      (node (ref "LED16") (pin "1") (pinfunction "BO_1") (pintype "input"))
      (node (ref "LED17") (pin "6") (pinfunction "BI_6") (pintype "input"))
    )
    (net (code "43") (name "Net-(LED16-DO)") (class "Default")
      (node (ref "LED16") (pin "3") (pinfunction "DO_3") (pintype "input"))
      (node (ref "LED17") (pin "4") (pinfunction "DI_4") (pintype "input"))
    )
    (net (code "44") (name "Net-(LED17-BO)") (class "Default")
      (node (ref "LED17") (pin "1") (pinfunction "BO_1") (pintype "input"))
      (node (ref "LED18") (pin "6") (pinfunction "BI_6") (pintype "input"))
    )
    (net (code "45") (name "Net-(LED17-DO)") (class "Default")
      (node (ref "LED17") (pin "3") (pinfunction "DO_3") (pintype "input"))
      (node (ref "LED18") (pin "4") (pinfunction "DI_4") (pintype "input"))
    )
    (net (code "46") (name "Net-(LED18-BO)") (class "Default")
      (node (ref "LED18") (pin "1") (pinfunction "BO_1") (pintype "input"))
      (node (ref "LED19") (pin "6") (pinfunction "BI_6") (pintype "input"))
    )
    (net (code "47") (name "Net-(LED18-DO)") (class "Default")
      (node (ref "LED18") (pin "3") (pinfunction "DO_3") (pintype "input"))
      (node (ref "LED19") (pin "4") (pinfunction "DI_4") (pintype "input"))
    )
    (net (code "48") (name "Net-(LED19-BO)") (class "Default")
      (node (ref "LED19") (pin "1") (pinfunction "BO_1") (pintype "input"))
      (node (ref "LED20") (pin "6") (pinfunction "BI_6") (pintype "input"))
    )
    (net (code "49") (name "Net-(LED19-DO)") (class "Default")
      (node (ref "LED19") (pin "3") (pinfunction "DO_3") (pintype "input"))
      (node (ref "LED20") (pin "4") (pinfunction "DI_4") (pintype "input"))
    )
    (net (code "50") (name "Net-(LED20-BO)") (class "Default")
      (node (ref "LED20") (pin "1") (pinfunction "BO_1") (pintype "input"))
      (node (ref "LED21") (pin "6") (pinfunction "BI_6") (pintype "input"))
    )
    (net (code "51") (name "Net-(LED20-DO)") (class "Default")
      (node (ref "LED20") (pin "3") (pinfunction "DO_3") (pintype "input"))
      (node (ref "LED21") (pin "4") (pinfunction "DI_4") (pintype "input"))
    )
    (net (code "52") (name "Net-(LED22-BO)") (class "Default")
      (node (ref "LED22") (pin "1") (pinfunction "BO_1") (pintype "input"))
      (node (ref "LED23") (pin "6") (pinfunction "BI_6") (pintype "input"))
    )
    (net (code "53") (name "Net-(LED22-DO)") (class "Default")
      (node (ref "LED22") (pin "3") (pinfunction "DO_3") (pintype "input"))
      (node (ref "LED23") (pin "4") (pinfunction "DI_4") (pintype "input"))
    )
    (net (code "54") (name "Net-(LED23-BO)") (class "Default")
      (node (ref "LED23") (pin "1") (pinfunction "BO_1") (pintype "input"))
      (node (ref "LED24") (pin "6") (pinfunction "BI_6") (pintype "input"))
    )
    (net (code "55") (name "Net-(LED23-DO)") (class "Default")
      (node (ref "LED23") (pin "3") (pinfunction "DO_3") (pintype "input"))
      (node (ref "LED24") (pin "4") (pinfunction "DI_4") (pintype "input"))
    )
    (net (code "56") (name "Net-(LED24-BO)") (class "Default")
      (node (ref "LED24") (pin "1") (pinfunction "BO_1") (pintype "input"))
      (node (ref "LED25") (pin "6") (pinfunction "BI_6") (pintype "input"))
    )
    (net (code "57") (name "Net-(LED24-DO)") (class "Default")
      (node (ref "LED24") (pin "3") (pinfunction "DO_3") (pintype "input"))
      (node (ref "LED25") (pin "4") (pinfunction "DI_4") (pintype "input"))
    )
    (net (code "58") (name "Net-(LED25-BO)") (class "Default")
      (node (ref "LED25") (pin "1") (pinfunction "BO_1") (pintype "input"))
      (node (ref "LED26") (pin "6") (pinfunction "BI_6") (pintype "input"))
    )
    (net (code "59") (name "Net-(LED25-DO)") (class "Default")
      (node (ref "LED25") (pin "3") (pinfunction "DO_3") (pintype "input"))
      (node (ref "LED26") (pin "4") (pinfunction "DI_4") (pintype "input"))
    )
    (net (code "60") (name "Net-(LED26-BO)") (class "Default")
      (node (ref "LED26") (pin "1") (pinfunction "BO_1") (pintype "input"))
      (node (ref "LED27") (pin "6") (pinfunction "BI_6") (pintype "input"))
    )
    (net (code "61") (name "Net-(LED26-DO)") (class "Default")
      (node (ref "LED26") (pin "3") (pinfunction "DO_3") (pintype "input"))
      (node (ref "LED27") (pin "4") (pinfunction "DI_4") (pintype "input"))
    )
    (net (code "62") (name "Net-(LED27-BO)") (class "Default")
      (node (ref "LED27") (pin "1") (pinfunction "BO_1") (pintype "input"))
      (node (ref "LED28") (pin "6") (pinfunction "BI_6") (pintype "input"))
    )
    (net (code "63") (name "Net-(LED27-DO)") (class "Default")
      (node (ref "LED27") (pin "3") (pinfunction "DO_3") (pintype "input"))
      (node (ref "LED28") (pin "4") (pinfunction "DI_4") (pintype "input"))
    )
    (net (code "64") (name "Net-(LED28-BO)") (class "Default")
      (node (ref "LED28") (pin "1") (pinfunction "BO_1") (pintype "input"))
      (node (ref "LED29") (pin "6") (pinfunction "BI_6") (pintype "input"))
    )
    (net (code "65") (name "Net-(LED28-DO)") (class "Default")
      (node (ref "LED28") (pin "3") (pinfunction "DO_3") (pintype "input"))
      (node (ref "LED29") (pin "4") (pinfunction "DI_4") (pintype "input"))
    )
    (net (code "66") (name "Net-(LED29-BO)") (class "Default")
      (node (ref "LED29") (pin "1") (pinfunction "BO_1") (pintype "input"))
      (node (ref "LED30") (pin "6") (pinfunction "BI_6") (pintype "input"))
    )
    (net (code "67") (name "Net-(LED29-DO)") (class "Default")
      (node (ref "LED29") (pin "3") (pinfunction "DO_3") (pintype "input"))
      (node (ref "LED30") (pin "4") (pinfunction "DI_4") (pintype "input"))
    )
    (net (code "68") (name "Net-(LED30-BO)") (class "Default")
      (node (ref "LED30") (pin "1") (pinfunction "BO_1") (pintype "input"))
      (node (ref "LED31") (pin "6") (pinfunction "BI_6") (pintype "input"))
    )
    (net (code "69") (name "Net-(LED30-DO)") (class "Default")
      (node (ref "LED30") (pin "3") (pinfunction "DO_3") (pintype "input"))
      (node (ref "LED31") (pin "4") (pinfunction "DI_4") (pintype "input"))
    )
    (net (code "70") (name "Net-(LED31-BO)") (class "Default")
      (node (ref "LED31") (pin "1") (pinfunction "BO_1") (pintype "input"))
      (node (ref "LED32") (pin "6") (pinfunction "BI_6") (pintype "input"))
    )
    (net (code "71") (name "Net-(LED31-DO)") (class "Default")
      (node (ref "LED31") (pin "3") (pinfunction "DO_3") (pintype "input"))
      (node (ref "LED32") (pin "4") (pinfunction "DI_4") (pintype "input"))
    )
    (net (code "72") (name "Net-(LED32-BO)") (class "Default")
      (node (ref "LED32") (pin "1") (pinfunction "BO_1") (pintype "input"))
      (node (ref "LED33") (pin "6") (pinfunction "BI_6") (pintype "input"))
    )
    (net (code "73") (name "Net-(LED32-DO)") (class "Default")
      (node (ref "LED32") (pin "3") (pinfunction "DO_3") (pintype "input"))
      (node (ref "LED33") (pin "4") (pinfunction "DI_4") (pintype "input"))
    )
    (net (code "74") (name "Net-(LED33-BO)") (class "Default")
      (node (ref "LED33") (pin "1") (pinfunction "BO_1") (pintype "input"))
      (node (ref "LED34") (pin "6") (pinfunction "BI_6") (pintype "input"))
    )
    (net (code "75") (name "Net-(LED33-DO)") (class "Default")
      (node (ref "LED33") (pin "3") (pinfunction "DO_3") (pintype "input"))
      (node (ref "LED34") (pin "4") (pinfunction "DI_4") (pintype "input"))
    )
    (net (code "76") (name "Net-(LED34-BO)") (class "Default")
      (node (ref "LED34") (pin "1") (pinfunction "BO_1") (pintype "input"))
      (node (ref "LED35") (pin "6") (pinfunction "BI_6") (pintype "input"))
    )
    (net (code "77") (name "Net-(LED34-DO)") (class "Default")
      (node (ref "LED34") (pin "3") (pinfunction "DO_3") (pintype "input"))
      (node (ref "LED35") (pin "4") (pinfunction "DI_4") (pintype "input"))
    )
    (net (code "78") (name "Net-(LED35-BO)") (class "Default")
      (node (ref "LED35") (pin "1") (pinfunction "BO_1") (pintype "input"))
      (node (ref "LED36") (pin "6") (pinfunction "BI_6") (pintype "input"))
    )
    (net (code "79") (name "Net-(LED35-DO)") (class "Default")
      (node (ref "LED35") (pin "3") (pinfunction "DO_3") (pintype "input"))
      (node (ref "LED36") (pin "4") (pinfunction "DI_4") (pintype "input"))
    )
    (net (code "80") (name "Net-(LED36-BO)") (class "Default")
      (node (ref "LED36") (pin "1") (pinfunction "BO_1") (pintype "input"))
      (node (ref "LED37") (pin "6") (pinfunction "BI_6") (pintype "input"))
    )
    (net (code "81") (name "Net-(LED36-DO)") (class "Default")
      (node (ref "LED36") (pin "3") (pinfunction "DO_3") (pintype "input"))
      (node (ref "LED37") (pin "4") (pinfunction "DI_4") (pintype "input"))
    )
    (net (code "82") (name "Net-(LED37-BO)") (class "Default")
      (node (ref "LED37") (pin "1") (pinfunction "BO_1") (pintype "input"))
      (node (ref "LED38") (pin "6") (pinfunction "BI_6") (pintype "input"))
    )
    (net (code "83") (name "Net-(LED37-DO)") (class "Default")
      (node (ref "LED37") (pin "3") (pinfunction "DO_3") (pintype "input"))
      (node (ref "LED38") (pin "4") (pinfunction "DI_4") (pintype "input"))
    )
    (net (code "84") (name "Net-(LED38-BO)") (class "Default")
      (node (ref "LED38") (pin "1") (pinfunction "BO_1") (pintype "input"))
      (node (ref "LED39") (pin "6") (pinfunction "BI_6") (pintype "input"))
    )
    (net (code "85") (name "Net-(LED38-DO)") (class "Default")
      (node (ref "LED38") (pin "3") (pinfunction "DO_3") (pintype "input"))
      (node (ref "LED39") (pin "4") (pinfunction "DI_4") (pintype "input"))
    )
    (net (code "86") (name "Net-(LED39-BO)") (class "Default")
      (node (ref "LED39") (pin "1") (pinfunction "BO_1") (pintype "input"))
      (node (ref "LED40") (pin "6") (pinfunction "BI_6") (pintype "input"))
    )
    (net (code "87") (name "Net-(LED39-DO)") (class "Default")
      (node (ref "LED39") (pin "3") (pinfunction "DO_3") (pintype "input"))
      (node (ref "LED40") (pin "4") (pinfunction "DI_4") (pintype "input"))
    )
    (net (code "88") (name "Net-(LED40-BO)") (class "Default")
      (node (ref "LED40") (pin "1") (pinfunction "BO_1") (pintype "input"))
      (node (ref "LED41") (pin "6") (pinfunction "BI_6") (pintype "input"))
    )
    (net (code "89") (name "Net-(LED40-DO)") (class "Default")
      (node (ref "LED40") (pin "3") (pinfunction "DO_3") (pintype "input"))
      (node (ref "LED41") (pin "4") (pinfunction "DI_4") (pintype "input"))
    )
    (net (code "90") (name "Net-(LED41-BO)") (class "Default")
      (node (ref "LED41") (pin "1") (pinfunction "BO_1") (pintype "input"))
      (node (ref "LED42") (pin "6") (pinfunction "BI_6") (pintype "input"))
    )
    (net (code "91") (name "Net-(LED41-DO)") (class "Default")
      (node (ref "LED41") (pin "3") (pinfunction "DO_3") (pintype "input"))
      (node (ref "LED42") (pin "4") (pinfunction "DI_4") (pintype "input"))
    )
    (net (code "92") (name "Net-(LED43-BO)") (class "Default")
      (node (ref "LED43") (pin "1") (pinfunction "BO_1") (pintype "input"))
      (node (ref "LED44") (pin "6") (pinfunction "BI_6") (pintype "input"))
    )
    (net (code "93") (name "Net-(LED43-DO)") (class "Default")
      (node (ref "LED43") (pin "3") (pinfunction "DO_3") (pintype "input"))
      (node (ref "LED44") (pin "4") (pinfunction "DI_4") (pintype "input"))
    )
    (net (code "94") (name "Net-(LED44-BO)") (class "Default")
      (node (ref "LED44") (pin "1") (pinfunction "BO_1") (pintype "input"))
      (node (ref "LED45") (pin "6") (pinfunction "BI_6") (pintype "input"))
    )
    (net (code "95") (name "Net-(LED44-DO)") (class "Default")
      (node (ref "LED44") (pin "3") (pinfunction "DO_3") (pintype "input"))
      (node (ref "LED45") (pin "4") (pinfunction "DI_4") (pintype "input"))
    )
    (net (code "96") (name "Net-(LED45-BO)") (class "Default")
      (node (ref "LED45") (pin "1") (pinfunction "BO_1") (pintype "input"))
      (node (ref "LED46") (pin "6") (pinfunction "BI_6") (pintype "input"))
    )
    (net (code "97") (name "Net-(LED45-DO)") (class "Default")
      (node (ref "LED45") (pin "3") (pinfunction "DO_3") (pintype "input"))
      (node (ref "LED46") (pin "4") (pinfunction "DI_4") (pintype "input"))
    )
    (net (code "98") (name "Net-(LED46-BO)") (class "Default")
      (node (ref "LED46") (pin "1") (pinfunction "BO_1") (pintype "input"))
      (node (ref "LED47") (pin "6") (pinfunction "BI_6") (pintype "input"))
    )
    (net (code "99") (name "Net-(LED46-DO)") (class "Default")
      (node (ref "LED46") (pin "3") (pinfunction "DO_3") (pintype "input"))
      (node (ref "LED47") (pin "4") (pinfunction "DI_4") (pintype "input"))
    )
    (net (code "100") (name "Net-(LED47-BO)") (class "Default")
      (node (ref "LED47") (pin "1") (pinfunction "BO_1") (pintype "input"))
      (node (ref "LED48") (pin "6") (pinfunction "BI_6") (pintype "input"))
    )
    (net (code "101") (name "Net-(LED47-DO)") (class "Default")
      (node (ref "LED47") (pin "3") (pinfunction "DO_3") (pintype "input"))
      (node (ref "LED48") (pin "4") (pinfunction "DI_4") (pintype "input"))
    )
    (net (code "102") (name "Net-(LED48-BO)") (class "Default")
      (node (ref "LED48") (pin "1") (pinfunction "BO_1") (pintype "input"))
      (node (ref "LED49") (pin "6") (pinfunction "BI_6") (pintype "input"))
    )
    (net (code "103") (name "Net-(LED48-DO)") (class "Default")
      (node (ref "LED48") (pin "3") (pinfunction "DO_3") (pintype "input"))
      (node (ref "LED49") (pin "4") (pinfunction "DI_4") (pintype "input"))
    )
    (net (code "104") (name "Net-(LED49-BO)") (class "Default")
      (node (ref "LED49") (pin "1") (pinfunction "BO_1") (pintype "input"))
      (node (ref "LED50") (pin "6") (pinfunction "BI_6") (pintype "input"))
    )
    (net (code "105") (name "Net-(LED49-DO)") (class "Default")
      (node (ref "LED49") (pin "3") (pinfunction "DO_3") (pintype "input"))
      (node (ref "LED50") (pin "4") (pinfunction "DI_4") (pintype "input"))
    )
    (net (code "106") (name "Net-(LED50-BO)") (class "Default")
      (node (ref "LED50") (pin "1") (pinfunction "BO_1") (pintype "input"))
      (node (ref "LED51") (pin "6") (pinfunction "BI_6") (pintype "input"))
    )
    (net (code "107") (name "Net-(LED50-DO)") (class "Default")
      (node (ref "LED50") (pin "3") (pinfunction "DO_3") (pintype "input"))
      (node (ref "LED51") (pin "4") (pinfunction "DI_4") (pintype "input"))
    )
    (net (code "108") (name "Net-(LED51-BO)") (class "Default")
      (node (ref "LED51") (pin "1") (pinfunction "BO_1") (pintype "input"))
      (node (ref "LED52") (pin "6") (pinfunction "BI_6") (pintype "input"))
    )
    (net (code "109") (name "Net-(LED51-DO)") (class "Default")
      (node (ref "LED51") (pin "3") (pinfunction "DO_3") (pintype "input"))
      (node (ref "LED52") (pin "4") (pinfunction "DI_4") (pintype "input"))
    )
    (net (code "110") (name "Net-(LED52-BO)") (class "Default")
      (node (ref "LED52") (pin "1") (pinfunction "BO_1") (pintype "input"))
      (node (ref "LED53") (pin "6") (pinfunction "BI_6") (pintype "input"))
    )
    (net (code "111") (name "Net-(LED52-DO)") (class "Default")
      (node (ref "LED52") (pin "3") (pinfunction "DO_3") (pintype "input"))
      (node (ref "LED53") (pin "4") (pinfunction "DI_4") (pintype "input"))
    )
    (net (code "112") (name "Net-(LED53-BO)") (class "Default")
      (node (ref "LED53") (pin "1") (pinfunction "BO_1") (pintype "input"))
      (node (ref "LED54") (pin "6") (pinfunction "BI_6") (pintype "input"))
    )
    (net (code "113") (name "Net-(LED53-DO)") (class "Default")
      (node (ref "LED53") (pin "3") (pinfunction "DO_3") (pintype "input"))
      (node (ref "LED54") (pin "4") (pinfunction "DI_4") (pintype "input"))
    )
    (net (code "114") (name "Net-(LED54-BO)") (class "Default")
      (node (ref "LED54") (pin "1") (pinfunction "BO_1") (pintype "input"))
      (node (ref "LED55") (pin "6") (pinfunction "BI_6") (pintype "input"))
    )
    (net (code "115") (name "Net-(LED54-DO)") (class "Default")
      (node (ref "LED54") (pin "3") (pinfunction "DO_3") (pintype "input"))
      (node (ref "LED55") (pin "4") (pinfunction "DI_4") (pintype "input"))
    )
    (net (code "116") (name "Net-(LED55-BO)") (class "Default")
      (node (ref "LED55") (pin "1") (pinfunction "BO_1") (pintype "input"))
      (node (ref "LED56") (pin "6") (pinfunction "BI_6") (pintype "input"))
    )
    (net (code "117") (name "Net-(LED55-DO)") (class "Default")
      (node (ref "LED55") (pin "3") (pinfunction "DO_3") (pintype "input"))
      (node (ref "LED56") (pin "4") (pinfunction "DI_4") (pintype "input"))
    )
    (net (code "118") (name "Net-(LED56-BO)") (class "Default")
      (node (ref "LED56") (pin "1") (pinfunction "BO_1") (pintype "input"))
      (node (ref "LED57") (pin "6") (pinfunction "BI_6") (pintype "input"))
    )
    (net (code "119") (name "Net-(LED56-DO)") (class "Default")
      (node (ref "LED56") (pin "3") (pinfunction "DO_3") (pintype "input"))
      (node (ref "LED57") (pin "4") (pinfunction "DI_4") (pintype "input"))
    )
    (net (code "120") (name "Net-(LED57-BO)") (class "Default")
      (node (ref "LED57") (pin "1") (pinfunction "BO_1") (pintype "input"))
      (node (ref "LED58") (pin "6") (pinfunction "BI_6") (pintype "input"))
    )
    (net (code "121") (name "Net-(LED57-DO)") (class "Default")
      (node (ref "LED57") (pin "3") (pinfunction "DO_3") (pintype "input"))
      (node (ref "LED58") (pin "4") (pinfunction "DI_4") (pintype "input"))
    )
    (net (code "122") (name "Net-(LED58-BO)") (class "Default")
      (node (ref "LED58") (pin "1") (pinfunction "BO_1") (pintype "input"))
      (node (ref "LED59") (pin "6") (pinfunction "BI_6") (pintype "input"))
    )
    (net (code "123") (name "Net-(LED58-DO)") (class "Default")
      (node (ref "LED58") (pin "3") (pinfunction "DO_3") (pintype "input"))
      (node (ref "LED59") (pin "4") (pinfunction "DI_4") (pintype "input"))
    )
    (net (code "124") (name "Net-(LED59-BO)") (class "Default")
      (node (ref "LED59") (pin "1") (pinfunction "BO_1") (pintype "input"))
      (node (ref "LED60") (pin "6") (pinfunction "BI_6") (pintype "input"))
    )
    (net (code "125") (name "Net-(LED59-DO)") (class "Default")
      (node (ref "LED59") (pin "3") (pinfunction "DO_3") (pintype "input"))
      (node (ref "LED60") (pin "4") (pinfunction "DI_4") (pintype "input"))
    )
    (net (code "126") (name "Net-(LED60-BO)") (class "Default")
      (node (ref "LED60") (pin "1") (pinfunction "BO_1") (pintype "input"))
      (node (ref "LED61") (pin "6") (pinfunction "BI_6") (pintype "input"))
    )
    (net (code "127") (name "Net-(LED60-DO)") (class "Default")
      (node (ref "LED60") (pin "3") (pinfunction "DO_3") (pintype "input"))
      (node (ref "LED61") (pin "4") (pinfunction "DI_4") (pintype "input"))
    )
    (net (code "128") (name "Net-(LED61-BO)") (class "Default")
      (node (ref "LED61") (pin "1") (pinfunction "BO_1") (pintype "input"))
      (node (ref "LED62") (pin "6") (pinfunction "BI_6") (pintype "input"))
    )
    (net (code "129") (name "Net-(LED61-DO)") (class "Default")
      (node (ref "LED61") (pin "3") (pinfunction "DO_3") (pintype "input"))
      (node (ref "LED62") (pin "4") (pinfunction "DI_4") (pintype "input"))
    )
    (net (code "130") (name "Net-(LED62-BO)") (class "Default")
      (node (ref "LED62") (pin "1") (pinfunction "BO_1") (pintype "input"))
      (node (ref "LED63") (pin "6") (pinfunction "BI_6") (pintype "input"))
    )
    (net (code "131") (name "Net-(LED62-DO)") (class "Default")
      (node (ref "LED62") (pin "3") (pinfunction "DO_3") (pintype "input"))
      (node (ref "LED63") (pin "4") (pinfunction "DI_4") (pintype "input"))
    )
    (net (code "132") (name "Net-(U2-BST)") (class "Default")
      (node (ref "C2") (pin "1") (pinfunction "1_1") (pintype "unspecified"))
      (node (ref "U2") (pin "6") (pinfunction "BST_6") (pintype "input"))
    )
    (net (code "133") (name "Net-(U2-SW)") (class "Default")
      (node (ref "C2") (pin "2") (pinfunction "2_2") (pintype "unspecified"))
      (node (ref "L1") (pin "1") (pinfunction "1_1") (pintype "unspecified"))
      (node (ref "U2") (pin "5") (pinfunction "SW_5") (pintype "input"))
    )
    (net (code "134") (name "VCC") (class "Default")
      (node (ref "C1") (pin "1") (pinfunction "1_1") (pintype "input"))
      (node (ref "H1") (pin "6") (pinfunction "6_6") (pintype "unspecified"))
      (node (ref "H2") (pin "6") (pinfunction "6_6") (pintype "unspecified"))
      (node (ref "U2") (pin "3") (pinfunction "VIN_3") (pintype "input"))
    )
  )
)
